# PCB_12V5A_60W.net
KiCad netlist of a schematic drawn in Altium Designer
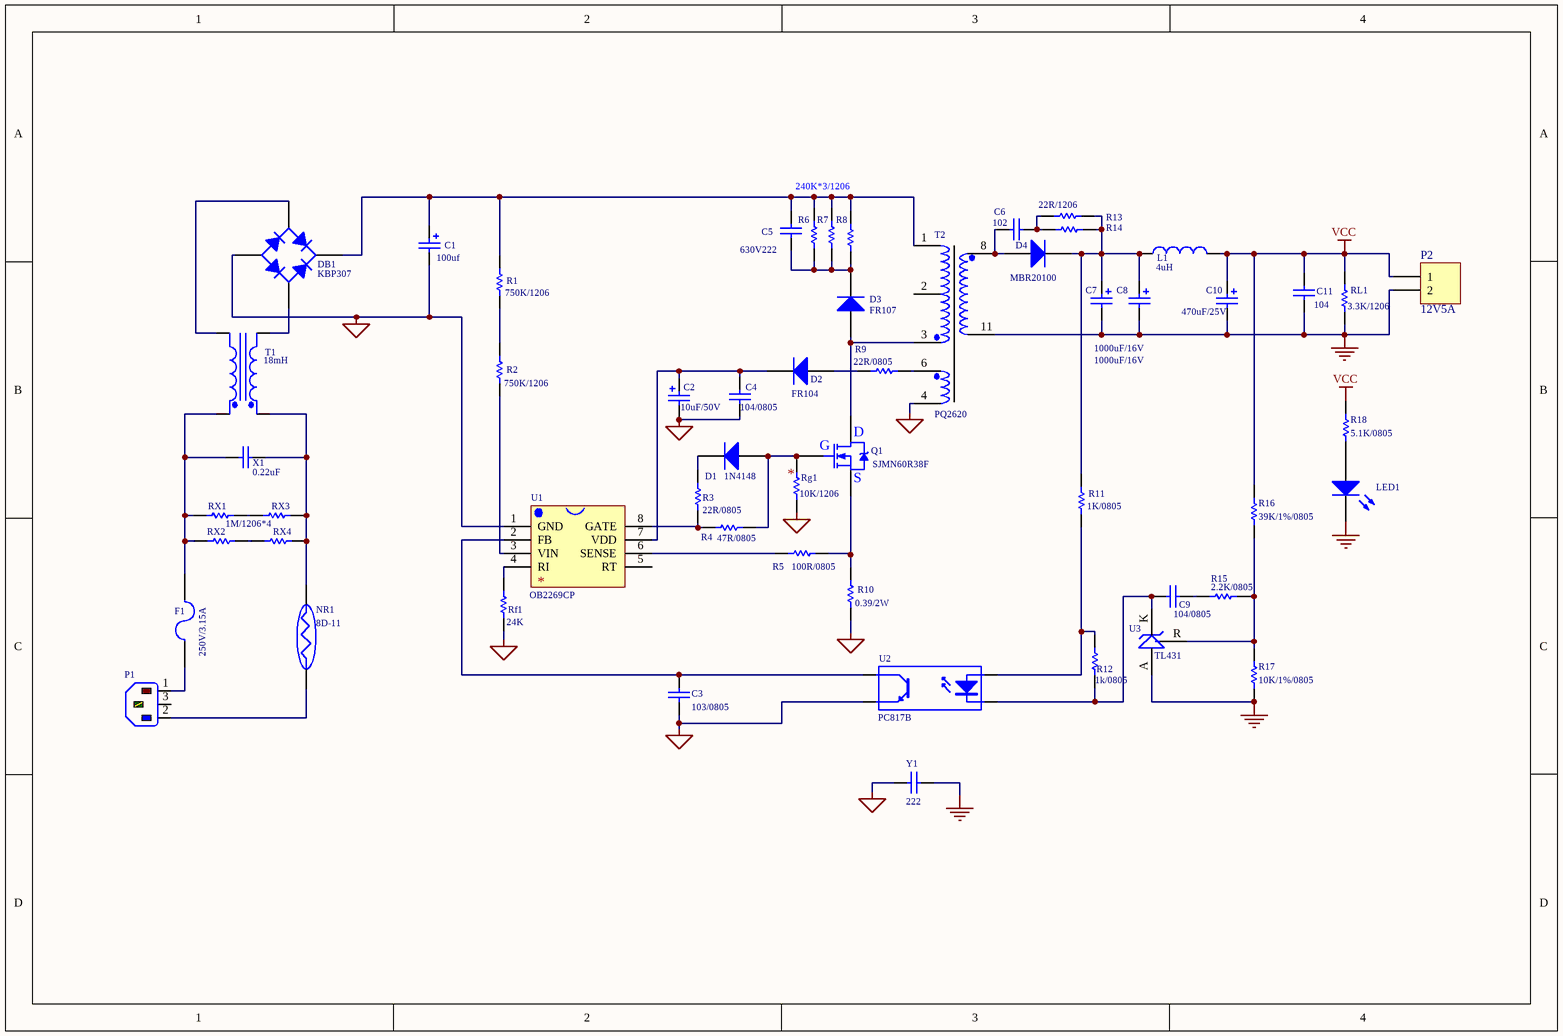
[diagram p0: PCB方案验证板  12V5A 60W.SchDoc]

(export (version "E")
  (design (tool "Eeschema 10.0.6"))
  (components
    (comp (ref "C1")
      (value "100uf")
      (footprint "Cin /400V/56uF Wo")
      (description "Polarized Capacitor (Axial)")
      (fields (field (name "PUBLISHER") "Altium Limited"))
      (libsource (lib "Miscellaneous Devices") (part "Cap Pol2"))
    )
    (comp (ref "C2")
      (value "10uF/50V")
      (footprint "C Φ5*11 L=2.5")
      (description "Polarized Capacitor (Axial)")
      (fields (field (name "Comment") "47uF/50V") (field (name "PUBLISHER") "Altium Limited"))
      (libsource (lib "Miscellaneous Devices") (part "Cap Pol2"))
    )
    (comp (ref "C3")
      (value "103/0805")
      (footprint "0805-C")
      (description "Capacitor")
      (fields (field (name "PUBLISHER") "Altium Limited"))
      (libsource (lib "Miscellaneous Devices") (part "Cap"))
    )
    (comp (ref "C4")
      (value "104/0805")
      (footprint "0805-C")
      (description "Capacitor")
      (fields (field (name "PUBLISHER") "Altium Limited"))
      (libsource (lib "Miscellaneous Devices") (part "Cap"))
    )
    (comp (ref "C5")
      (value "630V222")
      (footprint "CBB=7.5MM")
      (description "Capacitor")
      (fields (field (name "PUBLISHER") "Altium Limited"))
      (libsource (lib "Miscellaneous Devices") (part "Cap"))
    )
    (comp (ref "C6")
      (value "102")
      (footprint "1206-C")
      (description "Capacitor")
      (fields (field (name "Comment") "472") (field (name "PUBLISHER") "Altium Limited"))
      (libsource (lib "Miscellaneous Devices") (part "Cap"))
    )
    (comp (ref "C7")
      (value "1000uF/16V")
      (footprint "C 1000UF/16V")
      (description "Polarized Capacitor (Axial)")
      (fields (field (name "PUBLISHER") "Altium Limited"))
      (libsource (lib "") (part "Cap Pol2_1"))
    )
    (comp (ref "C8")
      (value "1000uF/16V")
      (footprint "C 1000UF/16V")
      (description "Polarized Capacitor (Axial)")
      (fields (field (name "PUBLISHER") "Altium Limited"))
      (libsource (lib "") (part "Cap Pol2_1"))
    )
    (comp (ref "C9")
      (value "104/0805")
      (footprint "0805-C")
      (description "Capacitor")
      (fields (field (name "PUBLISHER") "Altium Limited"))
      (libsource (lib "Miscellaneous Devices") (part "Cap"))
    )
    (comp (ref "C10")
      (value "470uF/25V")
      (footprint "C= 3.5MM 8*15")
      (description "Polarized Capacitor (Axial)")
      (fields (field (name "PUBLISHER") "Altium Limited"))
      (libsource (lib "") (part "Cap Pol2_1"))
    )
    (comp (ref "C11")
      (value "104")
      (footprint "1206-C")
      (description "Capacitor")
      (fields (field (name "PUBLISHER") "Altium Limited"))
      (libsource (lib "Miscellaneous Devices") (part "Cap"))
    )
    (comp (ref "D1")
      (value "1N4148")
      (footprint "D 1N4148")
      (description "Silicon Low Leakage Diode")
      (fields (field (name "PUBLISHER") "Altium Limited"))
      (libsource (lib "") (part "Diode BAS116_1"))
    )
    (comp (ref "D2")
      (value "FR104")
      (footprint "D/SOD123")
      (description "Silicon Low Leakage Diode")
      (fields (field (name "PUBLISHER") "Altium Limited"))
      (libsource (lib "Miscellaneous Devices") (part "Diode BAS116"))
    )
    (comp (ref "D3")
      (value "FR107")
      (footprint "D/SOD123")
      (description "Silicon Low Leakage Diode")
      (fields (field (name "PUBLISHER") "Altium Limited"))
      (libsource (lib "Miscellaneous Devices") (part "Diode BAS116"))
    )
    (comp (ref "D4")
      (value "MBR20100")
      (footprint "D TO-220")
      (description "Silicon Low Leakage Diode")
      (fields (field (name "PUBLISHER") "Altium Limited"))
      (libsource (lib "Miscellaneous Devices") (part "Diode BAS116"))
    )
    (comp (ref "DB1")
      (value "KBP307")
      (footprint "DB D=1.1MM")
      (description "Full Wave Diode Bridge")
      (fields (field (name "PUBLISHER") "Altium Limited"))
      (libsource (lib "Miscellaneous Devices") (part "Bridge1"))
    )
    (comp (ref "F1")
      (value "250V/3.15A")
      (footprint "F 3.15A L=5MM")
      (description "Fuse")
      (fields (field (name "PUBLISHER") "Altium Limited"))
      (libsource (lib "Miscellaneous Devices") (part "Fuse 2"))
    )
    (comp (ref "L1")
      (value "4uH")
      (footprint "L=7.6MM")
      (description "Inductor")
      (fields (field (name "PUBLISHER") "Altium Limited"))
      (libsource (lib "Miscellaneous Devices") (part "Inductor"))
    )
    (comp (ref "LED1")
      (value "LED1")
      (footprint "C0805")
      (description "Typical RED, GREEN, YELLOW, AMBER GaAs LED")
      (fields (field (name "PUBLISHER") "Altium Limited"))
      (libsource (lib "Miscellaneous Devices") (part "LED2"))
    )
    (comp (ref "NR1") (value "8D-11") (footprint "NTC=7.5mm") (libsource (lib "12V5A") (part "NTC")))
    (comp (ref "P1")
      (value "Plug AC Male")
      (footprint "AC IN")
      (description "IEC Mains Power Inlet, EN60 320-1 C14 Class I Cold Condition, PC Flange Rear Mount, Chassis Plug")
      (fields (field (name "PUBLISHER") "Altium Limited"))
      (libsource (lib "Miscellaneous Connectors") (part "Plug AC Male"))
    )
    (comp (ref "P2")
      (value "12V5A")
      (footprint "OUT")
      (description "Header, 2-Pin")
      (fields (field (name "PUBLISHER") "Altium Limited"))
      (libsource (lib "Miscellaneous Connectors") (part "Header 2"))
    )
    (comp (ref "Q1")
      (value "SJMN60R38F")
      (footprint "MOSFET1")
      (description "N-Channel Power MOSFET")
      (fields (field (name "PUBLISHER") "Altium Limited"))
      (libsource (lib "Miscellaneous Devices") (part "NMOS-2"))
    )
    (comp (ref "R1")
      (value "750K/1206")
      (footprint "1206-R")
      (description "Resistor")
      (fields (field (name "PUBLISHER") "Altium Limited"))
      (libsource (lib "Miscellaneous Devices") (part "Res1"))
    )
    (comp (ref "R2")
      (value "750K/1206")
      (footprint "1206-R")
      (description "Resistor")
      (fields (field (name "PUBLISHER") "Altium Limited"))
      (libsource (lib "Miscellaneous Devices") (part "Res1"))
    )
    (comp (ref "R3")
      (value "22R/0805")
      (footprint "0805-R")
      (description "Resistor")
      (fields (field (name "PUBLISHER") "Altium Limited"))
      (libsource (lib "Miscellaneous Devices") (part "Res1"))
    )
    (comp (ref "R4")
      (value "47R/0805")
      (footprint "0805-R")
      (description "Resistor")
      (fields (field (name "PUBLISHER") "Altium Limited"))
      (libsource (lib "Miscellaneous Devices") (part "Res1"))
    )
    (comp (ref "R5")
      (value "100R/0805")
      (footprint "0805-R")
      (description "Resistor")
      (fields (field (name "PUBLISHER") "Altium Limited"))
      (libsource (lib "Miscellaneous Devices") (part "Res1"))
    )
    (comp (ref "R6")
      (value "50K/2510/1W")
      (footprint "1206-R")
      (description "Resistor")
      (fields (field (name "PUBLISHER") "Altium Limited"))
      (libsource (lib "Miscellaneous Devices") (part "Res1"))
    )
    (comp (ref "R7")
      (value "50K/2510/1W")
      (footprint "1206-R")
      (description "Resistor")
      (fields (field (name "PUBLISHER") "Altium Limited"))
      (libsource (lib "Miscellaneous Devices") (part "Res1"))
    )
    (comp (ref "R8")
      (value "50K/2510/1W")
      (footprint "1206-R")
      (description "Resistor")
      (fields (field (name "PUBLISHER") "Altium Limited"))
      (libsource (lib "Miscellaneous Devices") (part "Res1"))
    )
    (comp (ref "R9")
      (value "22R/0805")
      (footprint "0805-R")
      (description "Resistor")
      (fields (field (name "PUBLISHER") "Altium Limited"))
      (libsource (lib "Miscellaneous Devices") (part "Res1"))
    )
    (comp (ref "R10")
      (value "0.39/2W")
      (footprint "R  2W")
      (description "Resistor")
      (fields (field (name "PUBLISHER") "Altium Limited"))
      (libsource (lib "Miscellaneous Devices") (part "Res1"))
    )
    (comp (ref "R11")
      (value "1K/0805")
      (footprint "0805-R")
      (description "Resistor")
      (fields (field (name "PUBLISHER") "Altium Limited"))
      (libsource (lib "Miscellaneous Devices") (part "Res1"))
    )
    (comp (ref "R12")
      (value "1k/0805")
      (footprint "0805-R")
      (description "Resistor")
      (fields (field (name "PUBLISHER") "Altium Limited"))
      (libsource (lib "Miscellaneous Devices") (part "Res1"))
    )
    (comp (ref "R13")
      (value "51R/1206")
      (footprint "1206-R")
      (description "Resistor")
      (fields (field (name "PUBLISHER") "Altium Limited"))
      (libsource (lib "Miscellaneous Devices") (part "Res1"))
    )
    (comp (ref "R14")
      (value "22R/1206")
      (footprint "1206-R")
      (description "Resistor")
      (fields (field (name "PUBLISHER") "Altium Limited"))
      (libsource (lib "Miscellaneous Devices") (part "Res1"))
    )
    (comp (ref "R15")
      (value "2.2K/0805")
      (footprint "0805-R")
      (description "Resistor")
      (fields (field (name "PUBLISHER") "Altium Limited"))
      (libsource (lib "Miscellaneous Devices") (part "Res1"))
    )
    (comp (ref "R16")
      (value "39K/1%/0805")
      (footprint "0805-R")
      (description "Resistor")
      (fields (field (name "PUBLISHER") "Altium Limited"))
      (libsource (lib "Miscellaneous Devices") (part "Res1"))
    )
    (comp (ref "R17")
      (value "10K/1%/0805")
      (footprint "0805-R")
      (description "Resistor")
      (fields (field (name "Comment") "12.5K/1%/0805") (field (name "PUBLISHER") "Altium Limited"))
      (libsource (lib "Miscellaneous Devices") (part "Res1"))
    )
    (comp (ref "R18")
      (value "5.1K/0805")
      (footprint "0805-R")
      (description "Resistor")
      (fields (field (name "PUBLISHER") "Altium Limited"))
      (libsource (lib "Miscellaneous Devices") (part "Res1"))
    )
    (comp (ref "Rf1")
      (value "24K")
      (footprint "0805-R")
      (description "Resistor")
      (fields (field (name "Comment") "Res1") (field (name "PUBLISHER") "Altium Limited"))
      (libsource (lib "Miscellaneous Devices") (part "Res1"))
    )
    (comp (ref "Rg1")
      (value "10K/1206")
      (footprint "0805-R")
      (description "Resistor")
      (fields (field (name "Comment") "10K/0805") (field (name "PUBLISHER") "Altium Limited"))
      (libsource (lib "Miscellaneous Devices") (part "Res1"))
    )
    (comp (ref "RL1")
      (value "3.3K/1206")
      (footprint "1206-R")
      (description "Resistor")
      (fields (field (name "PUBLISHER") "Altium Limited"))
      (libsource (lib "Miscellaneous Devices") (part "Res1"))
    )
    (comp (ref "RX1")
      (value "1M/1206*4")
      (footprint "1206-R")
      (description "Resistor")
      (fields (field (name "PUBLISHER") "Altium Limited"))
      (libsource (lib "Miscellaneous Devices") (part "Res1"))
    )
    (comp (ref "RX2")
      (value "1M/1206")
      (footprint "1206-R")
      (description "Resistor")
      (fields (field (name "PUBLISHER") "Altium Limited"))
      (libsource (lib "Miscellaneous Devices") (part "Res1"))
    )
    (comp (ref "RX3")
      (value "1M/1206")
      (footprint "1206-R")
      (description "Resistor")
      (fields (field (name "PUBLISHER") "Altium Limited"))
      (libsource (lib "Miscellaneous Devices") (part "Res1"))
    )
    (comp (ref "RX4")
      (value "1M/1206")
      (footprint "1206-R")
      (description "Resistor")
      (fields (field (name "PUBLISHER") "Altium Limited"))
      (libsource (lib "Miscellaneous Devices") (part "Res1"))
    )
    (comp (ref "T1")
      (value "18mH")
      (footprint "LF=6.9MM")
      (description "Transformer (Ideal)")
      (fields (field (name "PUBLISHER") "Altium Limited"))
      (libsource (lib "Miscellaneous Devices") (part "Trans Ideal"))
    )
    (comp (ref "T2") (value "PQ2620") (footprint "T PQ2620") (libsource (lib "12V5A") (part "T")))
    (comp (ref "U1") (value "OB2269CP") (footprint "OB2269") (libsource (lib "12V5A") (part "OB2269CP")))
    (comp (ref "U2")
      (value "PC817B")
      (footprint "LC-SMD-4")
      (description "4-Pin Phototransistor Optocoupler")
      (fields (field (name "PUBLISHER") "Altium Limited"))
      (libsource (lib "Miscellaneous Devices") (part "Optoisolator1"))
    )
    (comp (ref "U3")
      (value "TL431")
      (footprint "LC-SOT-23(SOT-23-3)")
      (libsource (lib "12V5A") (part "TL431"))
    )
    (comp (ref "X1")
      (value "0.22uF")
      (footprint "CX=10mm")
      (description "Capacitor")
      (fields (field (name "Comment") "224") (field (name "PUBLISHER") "Altium Limited"))
      (libsource (lib "Miscellaneous Devices") (part "Cap"))
    )
    (comp (ref "Y1")
      (value "222")
      (footprint "Y2")
      (description "Capacitor")
      (fields (field (name "PUBLISHER") "Altium Limited"))
      (libsource (lib "Miscellaneous Devices") (part "Cap"))
    )
  )
  (nets
    (net (code "1") (name "GND") (class "Default")
      (node (ref "C10") (pin "1") (pinfunction "1_1") (pintype "passive"))
      (node (ref "C11") (pin "2") (pinfunction "2_2") (pintype "passive"))
      (node (ref "C7") (pin "1") (pinfunction "1_1") (pintype "passive"))
      (node (ref "C8") (pin "1") (pinfunction "1_1") (pintype "passive"))
      (node (ref "LED1") (pin "2") (pinfunction "K_2") (pintype "passive"))
      (node (ref "P2") (pin "GND") (pinfunction "2_GND") (pintype "passive"))
      (node (ref "R17") (pin "1") (pinfunction "1_1") (pintype "passive"))
      (node (ref "RL1") (pin "1") (pinfunction "1_1") (pintype "passive"))
      (node (ref "T2") (pin "11") (pintype "passive"))
      (node (ref "U3") (pin "A") (pinfunction "A_A") (pintype "passive"))
      (node (ref "Y1") (pin "2") (pinfunction "2_2") (pintype "passive"))
    )
    (net (code "2") (name "GND1") (class "Default")
      (node (ref "C1") (pin "2") (pinfunction "2_2") (pintype "passive"))
      (node (ref "C2") (pin "2") (pinfunction "2_2") (pintype "passive"))
      (node (ref "C3") (pin "1") (pinfunction "1_1") (pintype "passive"))
      (node (ref "C4") (pin "2") (pinfunction "2_2") (pintype "passive"))
      (node (ref "DB1") (pin "-") (pinfunction "2_-") (pintype "passive"))
      (node (ref "R10") (pin "1") (pinfunction "1_1") (pintype "passive"))
      (node (ref "Rf1") (pin "2") (pinfunction "2_2") (pintype "passive"))
      (node (ref "Rg1") (pin "2") (pinfunction "2_2") (pintype "passive"))
      (node (ref "T2") (pin "4") (pinfunction "4_4") (pintype "passive"))
      (node (ref "U1") (pin "1") (pinfunction "GND_1") (pintype "passive"))
      (node (ref "U2") (pin "E") (pinfunction "E_E") (pintype "passive"))
      (node (ref "Y1") (pin "1") (pinfunction "1_1") (pintype "passive"))
    )
    (net (code "3") (name "Net-(C6-Pad2)") (class "Default")
      (node (ref "C6") (pin "2") (pinfunction "2_2") (pintype "passive"))
      (node (ref "R13") (pin "2") (pinfunction "2_2") (pintype "passive"))
      (node (ref "R14") (pin "2") (pinfunction "2_2") (pintype "passive"))
    )
    (net (code "4") (name "Net-(C9-Pad1)") (class "Default")
      (node (ref "C9") (pin "1") (pinfunction "1_1") (pintype "passive"))
      (node (ref "R12") (pin "1") (pinfunction "1_1") (pintype "passive"))
      (node (ref "U2") (pin "K") (pinfunction "K_K") (pintype "passive"))
      (node (ref "U3") (pin "K") (pinfunction "K_K") (pintype "passive"))
    )
    (net (code "5") (name "Net-(C9-Pad2)") (class "Default")
      (node (ref "C9") (pin "2") (pinfunction "2_2") (pintype "passive"))
      (node (ref "R15") (pin "2") (pinfunction "2_2") (pintype "passive"))
    )
    (net (code "6") (name "Net-(D1-A)") (class "Default")
      (node (ref "D1") (pin "+") (pinfunction "A_+") (pintype "passive"))
      (node (ref "Q1") (pin "G") (pinfunction "G_G") (pintype "passive"))
      (node (ref "R4") (pin "1") (pinfunction "1_1") (pintype "passive"))
      (node (ref "Rg1") (pin "1") (pinfunction "1_1") (pintype "passive"))
    )
    (net (code "7") (name "Net-(D1-K)") (class "Default")
      (node (ref "D1") (pin "-") (pinfunction "K_-") (pintype "passive"))
      (node (ref "R3") (pin "1") (pinfunction "1_1") (pintype "passive"))
    )
    (net (code "8") (name "Net-(D2-A)") (class "Default")
      (node (ref "D2") (pin "1") (pinfunction "A_1") (pintype "passive"))
      (node (ref "R9") (pin "2") (pinfunction "2_2") (pintype "passive"))
    )
    (net (code "9") (name "Net-(D2-K)") (class "Default")
      (node (ref "C2") (pin "1") (pinfunction "1_1") (pintype "passive"))
      (node (ref "C4") (pin "1") (pinfunction "1_1") (pintype "passive"))
      (node (ref "D2") (pin "2") (pinfunction "K_2") (pintype "passive"))
      (node (ref "U1") (pin "7") (pinfunction "VDD_7") (pintype "passive"))
    )
    (net (code "10") (name "Net-(D3-A)") (class "Default")
      (node (ref "D3") (pin "1") (pinfunction "A_1") (pintype "passive"))
      (node (ref "Q1") (pin "D") (pinfunction "D_D") (pintype "passive"))
      (node (ref "T2") (pin "3") (pintype "passive"))
    )
    (net (code "11") (name "Net-(D3-K)") (class "Default")
      (node (ref "C5") (pin "2") (pinfunction "2_2") (pintype "passive"))
      (node (ref "D3") (pin "2") (pinfunction "K_2") (pintype "passive"))
      (node (ref "R6") (pin "2") (pinfunction "2_2") (pintype "passive"))
      (node (ref "R7") (pin "2") (pinfunction "2_2") (pintype "passive"))
      (node (ref "R8") (pin "2") (pinfunction "2_2") (pintype "passive"))
    )
    (net (code "12") (name "Net-(D4-A)") (class "Default")
      (node (ref "C6") (pin "1") (pinfunction "1_1") (pintype "passive"))
      (node (ref "D4") (pin "1") (pinfunction "A_1") (pintype "passive"))
      (node (ref "T2") (pin "8") (pinfunction "6_8") (pintype "passive"))
    )
    (net (code "13") (name "Net-(D4-K)") (class "Default")
      (node (ref "C7") (pin "2") (pinfunction "2_2") (pintype "passive"))
      (node (ref "C8") (pin "2") (pinfunction "2_2") (pintype "passive"))
      (node (ref "D4") (pin "2") (pinfunction "K_2") (pintype "passive"))
      (node (ref "L1") (pin "1") (pinfunction "1_1") (pintype "passive"))
      (node (ref "R11") (pin "2") (pinfunction "2_2") (pintype "passive"))
      (node (ref "R13") (pin "1") (pinfunction "1_1") (pintype "passive"))
      (node (ref "R14") (pin "1") (pinfunction "1_1") (pintype "passive"))
    )
    (net (code "14") (name "Net-(DB1-1)") (class "Default")
      (node (ref "C1") (pin "1") (pinfunction "1_1") (pintype "passive"))
      (node (ref "C5") (pin "1") (pinfunction "1_1") (pintype "passive"))
      (node (ref "DB1") (pin "+") (pinfunction "1_+") (pintype "passive"))
      (node (ref "R1") (pin "2") (pinfunction "2_2") (pintype "passive"))
      (node (ref "R6") (pin "1") (pinfunction "1_1") (pintype "passive"))
      (node (ref "R7") (pin "1") (pinfunction "1_1") (pintype "passive"))
      (node (ref "R8") (pin "1") (pinfunction "1_1") (pintype "passive"))
      (node (ref "T2") (pin "1") (pintype "passive"))
    )
    (net (code "15") (name "Net-(DB1-3)") (class "Default")
      (node (ref "DB1") (pin "N") (pinfunction "3_N") (pintype "passive"))
      (node (ref "T1") (pin "4") (pinfunction "Pri-_4") (pintype "passive"))
    )
    (net (code "16") (name "Net-(DB1-4)") (class "Default")
      (node (ref "DB1") (pin "L") (pinfunction "4_L") (pintype "passive"))
      (node (ref "T1") (pin "2") (pinfunction "Sec-_2") (pintype "passive"))
    )
    (net (code "17") (name "Net-(LED1-A)") (class "Default")
      (node (ref "LED1") (pin "1") (pinfunction "A_1") (pintype "passive"))
      (node (ref "R18") (pin "1") (pinfunction "1_1") (pintype "passive"))
    )
    (net (code "18") (name "Net-(P1-L)") (class "Default")
      (node (ref "F1") (pin "1") (pinfunction "1_1") (pintype "passive"))
      (node (ref "P1") (pin "1") (pinfunction "L_1") (pintype "power_in"))
    )
    (net (code "19") (name "Net-(P1-N)") (class "Default")
      (node (ref "NR1") (pin "2") (pinfunction "2_2") (pintype "passive"))
      (node (ref "P1") (pin "2") (pinfunction "N_2") (pintype "power_in"))
    )
    (net (code "20") (name "Net-(Q1-PadS)") (class "Default")
      (node (ref "Q1") (pin "S") (pinfunction "S_S") (pintype "passive"))
      (node (ref "R10") (pin "2") (pinfunction "2_2") (pintype "passive"))
      (node (ref "R5") (pin "1") (pinfunction "1_1") (pintype "passive"))
    )
    (net (code "21") (name "Net-(R1-Pad1)") (class "Default")
      (node (ref "R1") (pin "1") (pinfunction "1_1") (pintype "passive"))
      (node (ref "R2") (pin "2") (pinfunction "2_2") (pintype "passive"))
    )
    (net (code "22") (name "Net-(R9-Pad1)") (class "Default")
      (node (ref "R9") (pin "1") (pinfunction "1_1") (pintype "passive"))
      (node (ref "T2") (pin "6") (pintype "passive"))
    )
    (net (code "23") (name "Net-(R11-Pad1)") (class "Default")
      (node (ref "R11") (pin "1") (pinfunction "1_1") (pintype "passive"))
      (node (ref "R12") (pin "2") (pinfunction "2_2") (pintype "passive"))
      (node (ref "U2") (pin "A") (pinfunction "A_A") (pintype "passive"))
    )
    (net (code "24") (name "Net-(R15-Pad1)") (class "Default")
      (node (ref "R15") (pin "1") (pinfunction "1_1") (pintype "passive"))
      (node (ref "R16") (pin "1") (pinfunction "1_1") (pintype "passive"))
      (node (ref "R17") (pin "2") (pinfunction "2_2") (pintype "passive"))
      (node (ref "U3") (pin "R") (pinfunction "R_R") (pintype "passive"))
    )
    (net (code "25") (name "Net-(RX1-Pad2)") (class "Default")
      (node (ref "RX1") (pin "2") (pinfunction "2_2") (pintype "passive"))
      (node (ref "RX3") (pin "1") (pinfunction "1_1") (pintype "passive"))
    )
    (net (code "26") (name "Net-(RX2-Pad2)") (class "Default")
      (node (ref "RX2") (pin "2") (pinfunction "2_2") (pintype "passive"))
      (node (ref "RX4") (pin "1") (pinfunction "1_1") (pintype "passive"))
    )
    (net (code "27") (name "Net-(T1-Pri+)") (class "Default")
      (node (ref "NR1") (pin "1") (pinfunction "1_1") (pintype "passive"))
      (node (ref "RX3") (pin "2") (pinfunction "2_2") (pintype "passive"))
      (node (ref "RX4") (pin "2") (pinfunction "2_2") (pintype "passive"))
      (node (ref "T1") (pin "1") (pinfunction "Pri+_1") (pintype "passive"))
      (node (ref "X1") (pin "2") (pinfunction "2_2") (pintype "passive"))
    )
    (net (code "28") (name "Net-(T1-Sec+)") (class "Default")
      (node (ref "F1") (pin "2") (pinfunction "2_2") (pintype "passive"))
      (node (ref "RX1") (pin "1") (pinfunction "1_1") (pintype "passive"))
      (node (ref "RX2") (pin "1") (pinfunction "1_1") (pintype "passive"))
      (node (ref "T1") (pin "3") (pinfunction "Sec+_3") (pintype "passive"))
      (node (ref "X1") (pin "1") (pinfunction "1_1") (pintype "passive"))
    )
    (net (code "29") (name "Net-(U1-FB)") (class "Default")
      (node (ref "C3") (pin "2") (pinfunction "2_2") (pintype "passive"))
      (node (ref "U1") (pin "2") (pinfunction "FB_2") (pintype "passive"))
      (node (ref "U2") (pin "C") (pinfunction "C_C") (pintype "passive"))
    )
    (net (code "30") (name "Net-(U1-GATE)") (class "Default")
      (node (ref "R3") (pin "2") (pinfunction "2_2") (pintype "passive"))
      (node (ref "R4") (pin "2") (pinfunction "2_2") (pintype "passive"))
      (node (ref "U1") (pin "8") (pinfunction "GATE_8") (pintype "passive"))
    )
    (net (code "31") (name "Net-(U1-RI)") (class "Default")
      (node (ref "Rf1") (pin "1") (pinfunction "1_1") (pintype "passive"))
      (node (ref "U1") (pin "4") (pinfunction "RI_4") (pintype "passive"))
    )
    (net (code "32") (name "Net-(U1-SENSE)") (class "Default")
      (node (ref "R5") (pin "2") (pinfunction "2_2") (pintype "passive"))
      (node (ref "U1") (pin "6") (pinfunction "SENSE_6") (pintype "passive"))
    )
    (net (code "33") (name "Net-(U1-VIN)") (class "Default")
      (node (ref "R2") (pin "1") (pinfunction "1_1") (pintype "passive"))
      (node (ref "U1") (pin "3") (pinfunction "VIN_3") (pintype "passive"))
    )
    (net (code "34") (name "VCC") (class "Default")
      (node (ref "C10") (pin "2") (pinfunction "2_2") (pintype "passive"))
      (node (ref "C11") (pin "1") (pinfunction "1_1") (pintype "passive"))
      (node (ref "L1") (pin "2") (pinfunction "2_2") (pintype "passive"))
      (node (ref "P2") (pin "VCC") (pinfunction "1_VCC") (pintype "passive"))
      (node (ref "R16") (pin "2") (pinfunction "2_2") (pintype "passive"))
      (node (ref "R18") (pin "2") (pinfunction "2_2") (pintype "passive"))
      (node (ref "RL1") (pin "2") (pinfunction "2_2") (pintype "passive"))
    )
    (net (code "35") (name "unconnected-(P1-E-Pad3)") (class "Default")
      (node (ref "P1") (pin "3") (pinfunction "E_3") (pintype "power_in"))
    )
    (net (code "36") (name "unconnected-(T2-Pad2)") (class "Default")
      (node (ref "T2") (pin "2") (pintype "passive"))
    )
    (net (code "37") (name "unconnected-(U1-RT-Pad5)") (class "Default")
      (node (ref "U1") (pin "5") (pinfunction "RT_5") (pintype "passive"))
    )
  )
)
